# Becca_Sap_Flow_Power_Board_v1_3.net
KiCad netlist of a schematic drawn in EAGLE
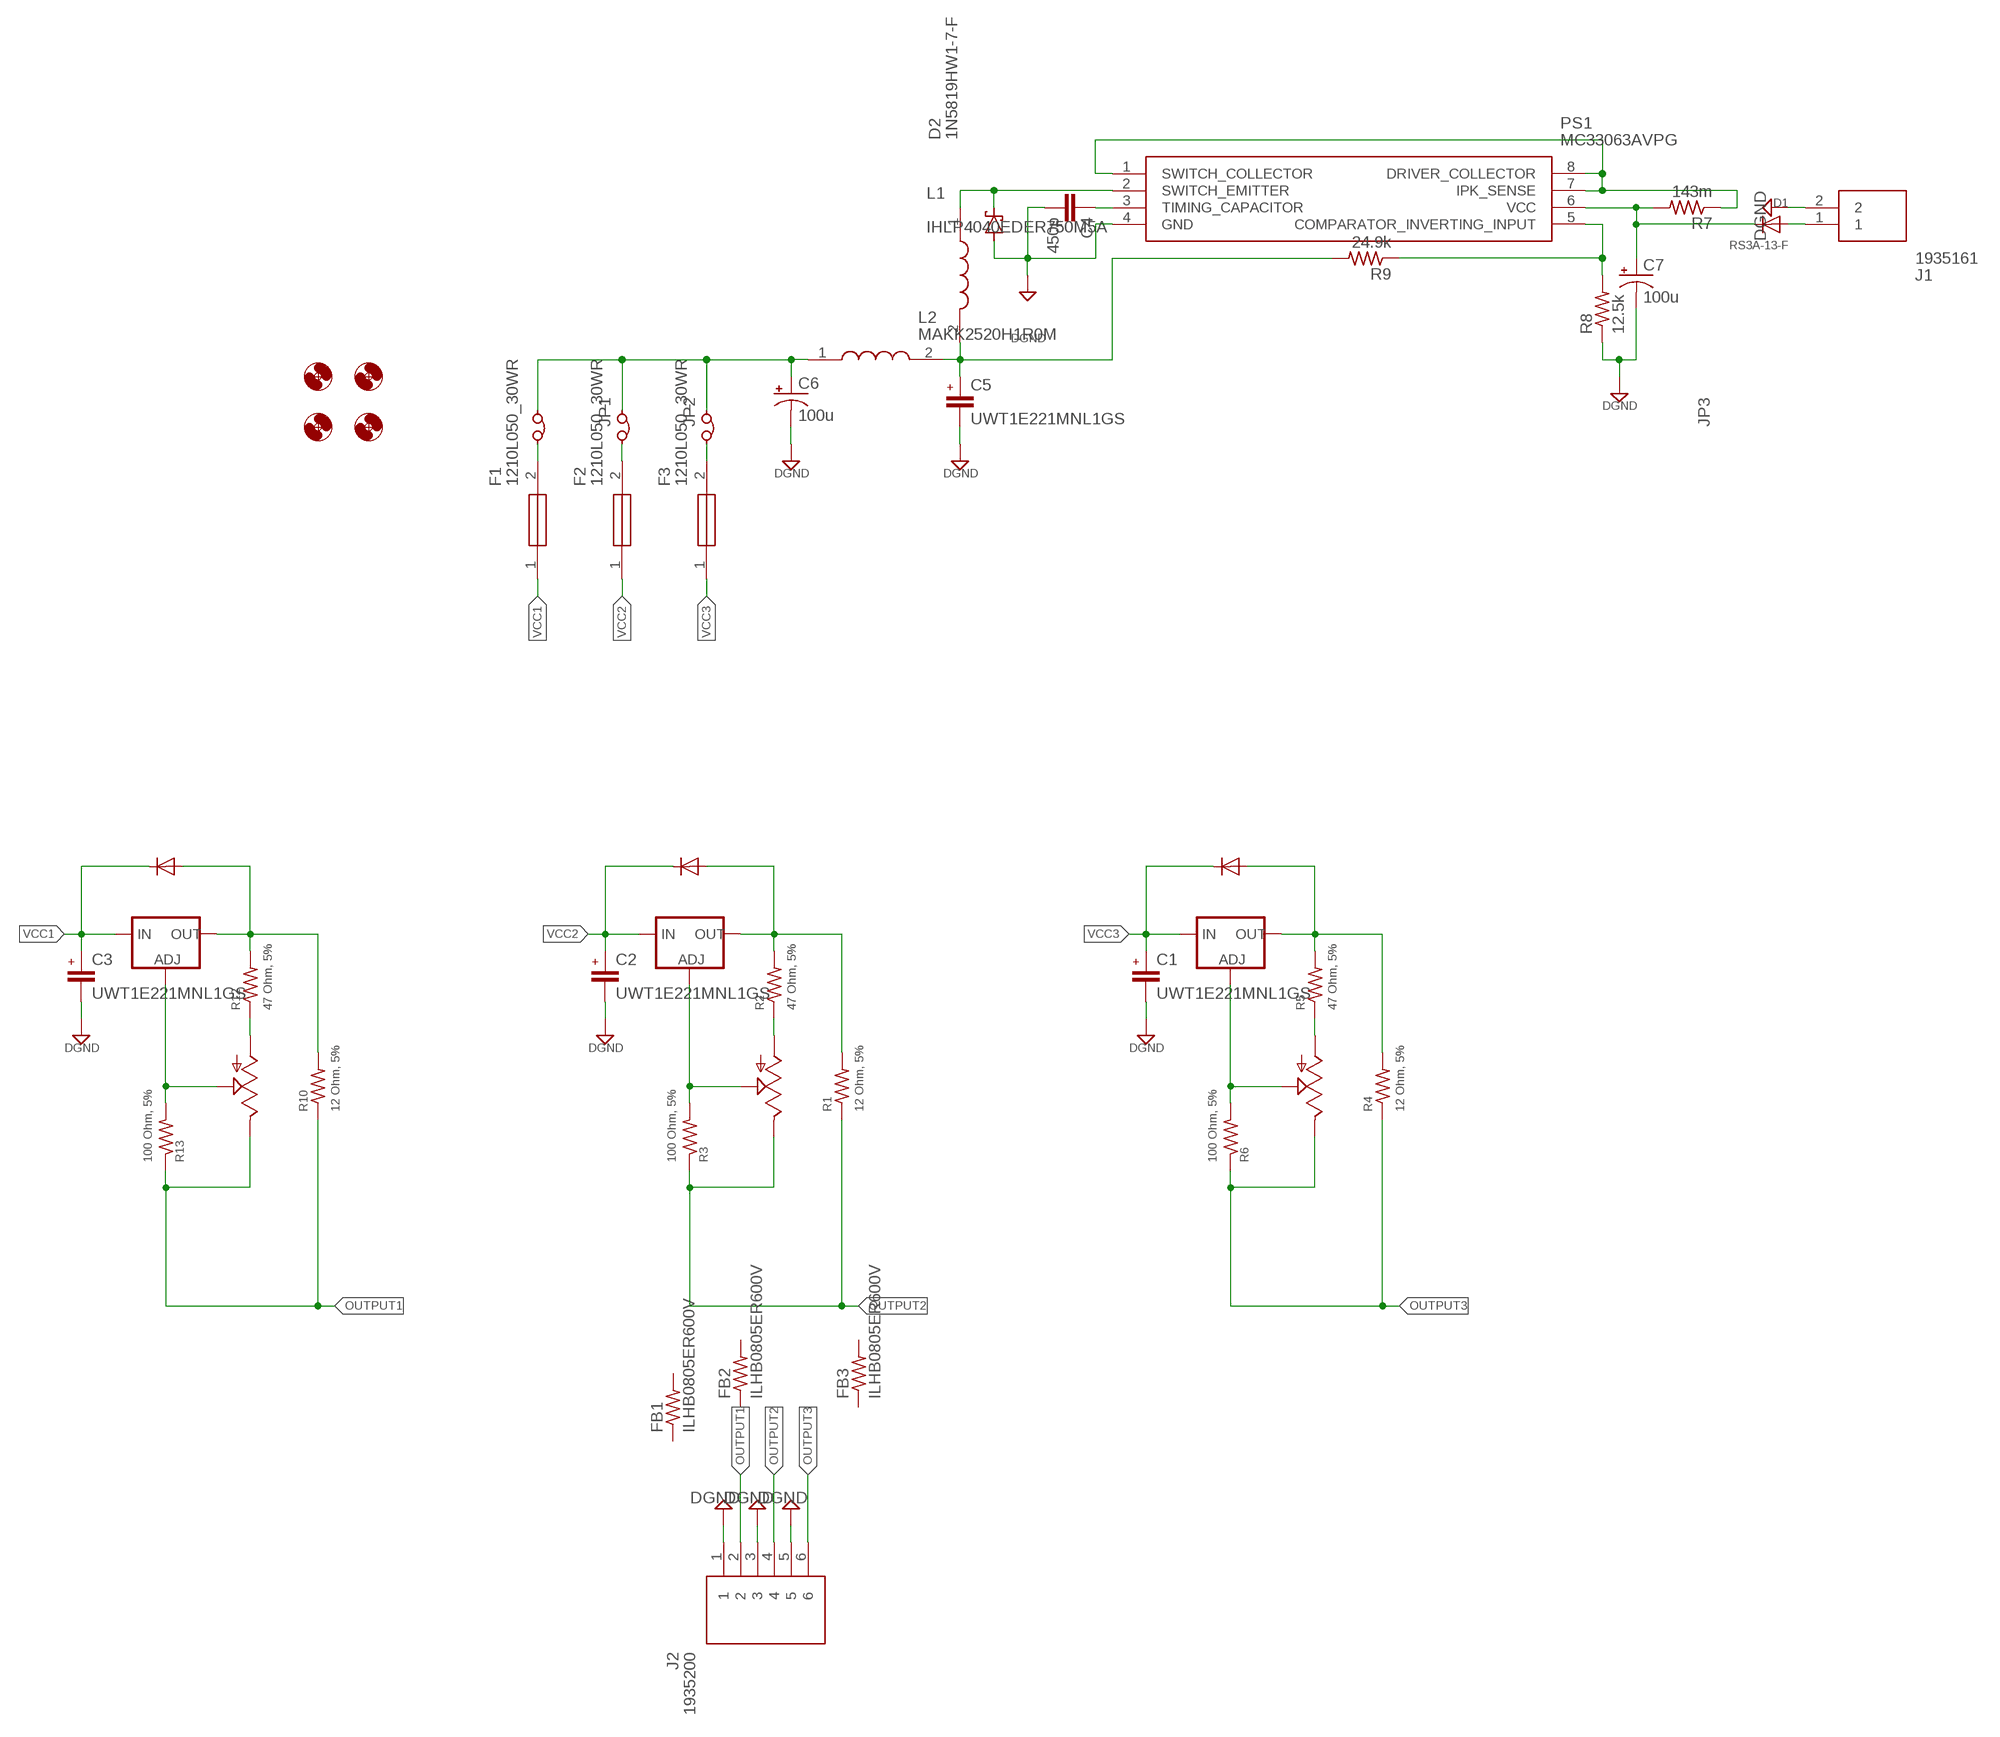
[diagram p0: schematic, sheet 1]

(export (version "E")
  (design (tool "Eeschema 10.0.6"))
  (components
    (comp (ref "C1")
      (value "UWT1E221MNL1GS")
      (footprint "eagle-import:CAPAE830X1080N")
      (fields (field (name "MOUSER_PART_NUMBER") "647-UWT1E221MNL1GS"))
      (libsource (lib "eagle-import") (part "UWT1E221MNL1GS"))
    )
    (comp (ref "C2")
      (value "UWT1E221MNL1GS")
      (footprint "eagle-import:CAPAE830X1080N")
      (fields (field (name "MOUSER_PART_NUMBER") "647-UWT1E221MNL1GS"))
      (libsource (lib "eagle-import") (part "UWT1E221MNL1GS"))
    )
    (comp (ref "C3")
      (value "UWT1E221MNL1GS")
      (footprint "eagle-import:CAPAE830X1080N")
      (fields (field (name "MOUSER_PART_NUMBER") "647-UWT1E221MNL1GS"))
      (libsource (lib "eagle-import") (part "UWT1E221MNL1GS"))
    )
    (comp (ref "C4")
      (value "450p")
      (footprint "eagle-import:C0603")
      (libsource (lib "eagle-import") (part "C-EUC0603"))
    )
    (comp (ref "C5")
      (value "UWT1E221MNL1GS")
      (footprint "eagle-import:CAPAE830X1080N")
      (fields (field (name "MOUSER_PART_NUMBER") "647-UWT1E221MNL1GS"))
      (libsource (lib "eagle-import") (part "UWT1E221MNL1GS"))
    )
    (comp (ref "C6")
      (value "100u")
      (footprint "eagle-import:E2,5-6")
      (libsource (lib "eagle-import") (part "CPOL-USE2.5-6"))
    )
    (comp (ref "C7")
      (value "100u")
      (footprint "eagle-import:E2,5-6")
      (libsource (lib "eagle-import") (part "CPOL-USE2.5-6"))
    )
    (comp (ref "D1")
      (value "RS3A-13-F")
      (footprint "eagle-import:DIOM7959X250N")
      (fields (field (name "MOUSER_PART_NUMBER") "621-RS3A-13-F"))
      (libsource (lib "eagle-import") (part "RS3A-13-F"))
    )
    (comp (ref "D2")
      (value "1N5819HW1-7-F")
      (footprint "eagle-import:SODFL3518X115N")
      (fields (field (name "MOUSER_PART_NUMBER") "621-1N5819HW1-7-F"))
      (libsource (lib "eagle-import") (part "1N5819HW1-7-F"))
    )
    (comp (ref "D3")
      (value "S1A")
      (footprint "eagle-import:DIOM5027X250N")
      (fields (field (name "MOUSER_PART_NUMBER") "637-S1A"))
      (libsource (lib "eagle-import") (part "S1A"))
    )
    (comp (ref "D4")
      (value "S1A")
      (footprint "eagle-import:DIOM5027X250N")
      (fields (field (name "MOUSER_PART_NUMBER") "637-S1A"))
      (libsource (lib "eagle-import") (part "S1A"))
    )
    (comp (ref "D6")
      (value "S1A")
      (footprint "eagle-import:DIOM5027X250N")
      (fields (field (name "MOUSER_PART_NUMBER") "637-S1A"))
      (libsource (lib "eagle-import") (part "S1A"))
    )
    (comp (ref "F1")
      (value "1210L050_30WR")
      (footprint "eagle-import:THRMC3226X125N")
      (fields
        (field (name "MANUFACTURER_PART_NUMBER") "1210L050/30WR")
        (field (name "MOUSER_PART_NUMBER") "576-1210L050/30WR")
      )
      (libsource (lib "eagle-import") (part "1210L050_30WR"))
    )
    (comp (ref "F2")
      (value "1210L050_30WR")
      (footprint "eagle-import:THRMC3226X125N")
      (fields
        (field (name "MANUFACTURER_PART_NUMBER") "1210L050/30WR")
        (field (name "MOUSER_PART_NUMBER") "576-1210L050/30WR")
      )
      (libsource (lib "eagle-import") (part "1210L050_30WR"))
    )
    (comp (ref "F3")
      (value "1210L050_30WR")
      (footprint "eagle-import:THRMC3226X125N")
      (fields
        (field (name "MANUFACTURER_PART_NUMBER") "1210L050/30WR")
        (field (name "MOUSER_PART_NUMBER") "576-1210L050/30WR")
      )
      (libsource (lib "eagle-import") (part "1210L050_30WR"))
    )
    (comp (ref "FB1")
      (value "ILHB0805ER600V")
      (footprint "eagle-import:BEADC2012X110N")
      (fields (field (name "MOUSER_PART_NUMBER") "70-ILHB0805ER600V"))
      (libsource (lib "eagle-import") (part "ILHB0805ER600V"))
    )
    (comp (ref "FB2")
      (value "ILHB0805ER600V")
      (footprint "eagle-import:BEADC2012X110N")
      (fields (field (name "MOUSER_PART_NUMBER") "70-ILHB0805ER600V"))
      (libsource (lib "eagle-import") (part "ILHB0805ER600V"))
    )
    (comp (ref "FB3")
      (value "ILHB0805ER600V")
      (footprint "eagle-import:BEADC2012X110N")
      (fields (field (name "MOUSER_PART_NUMBER") "70-ILHB0805ER600V"))
      (libsource (lib "eagle-import") (part "ILHB0805ER600V"))
    )
    (comp (ref "J1")
      (value "1935161")
      (footprint "eagle-import:1935161")
      (fields (field (name "MOUSER_PART_NUMBER") "651-1935161"))
      (libsource (lib "eagle-import") (part "1935161"))
    )
    (comp (ref "J2")
      (value "1935200")
      (footprint "eagle-import:1935200")
      (fields (field (name "MOUSER_PART_NUMBER") "651-1935200"))
      (libsource (lib "eagle-import") (part "1935200"))
    )
    (comp (ref "JP1")
      (value "JUMPER")
      (footprint "eagle-import:HDR2X1")
      (libsource (lib "eagle-import") (part "JUMPER"))
    )
    (comp (ref "JP2")
      (value "JUMPER")
      (footprint "eagle-import:HDR2X1")
      (libsource (lib "eagle-import") (part "JUMPER"))
    )
    (comp (ref "JP3")
      (value "JUMPER")
      (footprint "eagle-import:HDR2X1")
      (libsource (lib "eagle-import") (part "JUMPER"))
    )
    (comp (ref "L1")
      (value "IHLP4040EDER750M5A")
      (footprint "eagle-import:INDPM115103X540N")
      (fields (field (name "MOUSER_PART_NUMBER") "70-IHLP4040EDR750M5A"))
      (libsource (lib "eagle-import") (part "IHLP4040EDER750M5A"))
    )
    (comp (ref "L2")
      (value "MAKK2520H1R0M")
      (footprint "eagle-import:MAKK2520H1R0M")
      (fields (field (name "MOUSER_PART_NUMBER") "963-MAKK2520H1R0M"))
      (libsource (lib "eagle-import") (part "MAKK2520H1R0M"))
    )
    (comp (ref "PS1")
      (value "MC33063AVPG")
      (footprint "eagle-import:DIP794W56P254L959H533Q8N")
      (libsource (lib "eagle-import") (part "MC33063AVPG"))
    )
    (comp (ref "R1")
      (value "12 Ohm, 5%")
      (footprint "eagle-import:R1210")
      (libsource (lib "eagle-import") (part "R-US_R1210"))
    )
    (comp (ref "R2")
      (value "47 Ohm, 5%")
      (footprint "eagle-import:R1210")
      (libsource (lib "eagle-import") (part "R-US_R1210"))
    )
    (comp (ref "R3")
      (value "100 Ohm, 5%")
      (footprint "eagle-import:R1210")
      (libsource (lib "eagle-import") (part "R-US_R1210"))
    )
    (comp (ref "R4")
      (value "12 Ohm, 5%")
      (footprint "eagle-import:R1210")
      (libsource (lib "eagle-import") (part "R-US_R1210"))
    )
    (comp (ref "R5")
      (value "47 Ohm, 5%")
      (footprint "eagle-import:R1210")
      (libsource (lib "eagle-import") (part "R-US_R1210"))
    )
    (comp (ref "R6")
      (value "100 Ohm, 5%")
      (footprint "eagle-import:R1210")
      (libsource (lib "eagle-import") (part "R-US_R1210"))
    )
    (comp (ref "R7")
      (value "143m")
      (footprint "eagle-import:R0603")
      (libsource (lib "eagle-import") (part "R-US_R0603"))
    )
    (comp (ref "R8")
      (value "12.5k")
      (footprint "eagle-import:R0603")
      (libsource (lib "eagle-import") (part "R-US_R0603"))
    )
    (comp (ref "R9")
      (value "24.9k")
      (footprint "eagle-import:R0603")
      (libsource (lib "eagle-import") (part "R-US_R0603"))
    )
    (comp (ref "R10")
      (value "12 Ohm, 5%")
      (footprint "eagle-import:R1210")
      (libsource (lib "eagle-import") (part "R-US_R1210"))
    )
    (comp (ref "R12")
      (value "47 Ohm, 5%")
      (footprint "eagle-import:R1210")
      (libsource (lib "eagle-import") (part "R-US_R1210"))
    )
    (comp (ref "R13")
      (value "100 Ohm, 5%")
      (footprint "eagle-import:R1210")
      (libsource (lib "eagle-import") (part "R-US_R1210"))
    )
    (comp (ref "U$1")
      (value "MOUNT-HOLE3.0")
      (footprint "eagle-import:3,0")
      (libsource (lib "eagle-import") (part "MOUNT-HOLE3.0"))
    )
    (comp (ref "U$2")
      (value "MOUNT-HOLE3.0")
      (footprint "eagle-import:3,0")
      (libsource (lib "eagle-import") (part "MOUNT-HOLE3.0"))
    )
    (comp (ref "U$3")
      (value "MOUNT-HOLE3.0")
      (footprint "eagle-import:3,0")
      (libsource (lib "eagle-import") (part "MOUNT-HOLE3.0"))
    )
    (comp (ref "U$4")
      (value "MOUNT-HOLE3.0")
      (footprint "eagle-import:3,0")
      (libsource (lib "eagle-import") (part "MOUNT-HOLE3.0"))
    )
    (comp (ref "U1")
      (value "LM317MBSTT3G")
      (footprint "eagle-import:SOT230P700X175-4N")
      (fields (field (name "MOUSER_PART_NUMBER") "863-LM317MBSTT3G"))
      (libsource (lib "eagle-import") (part "LM317MBSTT3G"))
    )
    (comp (ref "U2")
      (value "LM317MBSTT3G")
      (footprint "eagle-import:SOT230P700X175-4N")
      (fields (field (name "MOUSER_PART_NUMBER") "863-LM317MBSTT3G"))
      (libsource (lib "eagle-import") (part "LM317MBSTT3G"))
    )
    (comp (ref "U3")
      (value "LM317MBSTT3G")
      (footprint "eagle-import:SOT230P700X175-4N")
      (fields (field (name "MOUSER_PART_NUMBER") "863-LM317MBSTT3G"))
      (libsource (lib "eagle-import") (part "LM317MBSTT3G"))
    )
    (comp (ref "VR1")
      (value "3296W-1-102RLF")
      (footprint "eagle-import:3296W1102RLF")
      (fields (field (name "MOUSER_PART_NUMBER") "652-3296W-1-102RLF"))
      (libsource (lib "eagle-import") (part "3296W-1-102RLF"))
    )
    (comp (ref "VR2")
      (value "3296W-1-102RLF")
      (footprint "eagle-import:3296W1102RLF")
      (fields (field (name "MOUSER_PART_NUMBER") "652-3296W-1-102RLF"))
      (libsource (lib "eagle-import") (part "3296W-1-102RLF"))
    )
    (comp (ref "VR3")
      (value "3296W-1-102RLF")
      (footprint "eagle-import:3296W1102RLF")
      (fields (field (name "MOUSER_PART_NUMBER") "652-3296W-1-102RLF"))
      (libsource (lib "eagle-import") (part "3296W-1-102RLF"))
    )
  )
  (nets
    (net (code "1") (name "DGND") (class "Default")
      (node (ref "C1") (pin "2") (pinfunction "2_2") (pintype "passive"))
      (node (ref "C2") (pin "2") (pinfunction "2_2") (pintype "passive"))
      (node (ref "C3") (pin "2") (pinfunction "2_2") (pintype "passive"))
      (node (ref "C4") (pin "2") (pinfunction "2_2") (pintype "passive"))
      (node (ref "C5") (pin "2") (pinfunction "2_2") (pintype "passive"))
      (node (ref "C6") (pin "-") (pinfunction "-_-") (pintype "passive"))
      (node (ref "C7") (pin "-") (pinfunction "-_-") (pintype "passive"))
      (node (ref "D2") (pin "2") (pinfunction "A_2") (pintype "passive"))
      (node (ref "J1") (pin "2") (pinfunction "2_2") (pintype "bidirectional"))
      (node (ref "J2") (pin "1") (pinfunction "1_1") (pintype "bidirectional"))
      (node (ref "J2") (pin "3") (pinfunction "3_3") (pintype "bidirectional"))
      (node (ref "J2") (pin "5") (pinfunction "5_5") (pintype "bidirectional"))
      (node (ref "PS1") (pin "4") (pinfunction "GND_4") (pintype "bidirectional"))
      (node (ref "R8") (pin "1") (pinfunction "1_1") (pintype "passive"))
    )
    (net (code "2") (name "Net-(C5-Pad1)") (class "Default")
      (node (ref "C5") (pin "1") (pinfunction "1_1") (pintype "passive"))
      (node (ref "L1") (pin "2") (pinfunction "2_2") (pintype "bidirectional"))
      (node (ref "L2") (pin "2") (pinfunction "2_2") (pintype "bidirectional"))
      (node (ref "R9") (pin "2") (pinfunction "2_2") (pintype "passive"))
    )
    (net (code "3") (name "Net-(C6-Pad+)") (class "Default")
      (node (ref "C6") (pin "+") (pinfunction "+_+") (pintype "passive"))
      (node (ref "JP1") (pin "1") (pinfunction "1_1") (pintype "passive"))
      (node (ref "JP2") (pin "1") (pinfunction "1_1") (pintype "passive"))
      (node (ref "JP3") (pin "1") (pinfunction "1_1") (pintype "passive"))
      (node (ref "L2") (pin "1") (pinfunction "1_1") (pintype "bidirectional"))
    )
    (net (code "4") (name "Net-(D1-A)") (class "Default")
      (node (ref "D1") (pin "2") (pinfunction "A_2") (pintype "passive"))
      (node (ref "J1") (pin "1") (pinfunction "1_1") (pintype "bidirectional"))
    )
    (net (code "5") (name "Net-(D1-K)") (class "Default")
      (node (ref "C7") (pin "+") (pinfunction "+_+") (pintype "passive"))
      (node (ref "D1") (pin "1") (pinfunction "K_1") (pintype "passive"))
      (node (ref "PS1") (pin "6") (pinfunction "VCC_6") (pintype "bidirectional"))
      (node (ref "R7") (pin "2") (pinfunction "2_2") (pintype "passive"))
    )
    (net (code "6") (name "Net-(D2-C)") (class "Default")
      (node (ref "D2") (pin "1") (pinfunction "C_1") (pintype "passive"))
      (node (ref "L1") (pin "1") (pinfunction "1_1") (pintype "bidirectional"))
      (node (ref "PS1") (pin "2") (pinfunction "SWITCH_EMITTER_2") (pintype "bidirectional"))
    )
    (net (code "7") (name "Net-(D3-A)") (class "Default")
      (node (ref "D3") (pin "2") (pinfunction "A_2") (pintype "passive"))
      (node (ref "R1") (pin "2") (pinfunction "2_2") (pintype "passive"))
      (node (ref "R2") (pin "2") (pinfunction "2_2") (pintype "passive"))
      (node (ref "U2") (pin "2") (pinfunction "OUT_2") (pintype "output"))
    )
    (net (code "8") (name "Net-(D4-A)") (class "Default")
      (node (ref "D4") (pin "2") (pinfunction "A_2") (pintype "passive"))
      (node (ref "R4") (pin "2") (pinfunction "2_2") (pintype "passive"))
      (node (ref "R5") (pin "2") (pinfunction "2_2") (pintype "passive"))
      (node (ref "U3") (pin "2") (pinfunction "OUT_2") (pintype "output"))
    )
    (net (code "9") (name "Net-(D6-A)") (class "Default")
      (node (ref "D6") (pin "2") (pinfunction "A_2") (pintype "passive"))
      (node (ref "R10") (pin "2") (pinfunction "2_2") (pintype "passive"))
      (node (ref "R12") (pin "2") (pinfunction "2_2") (pintype "passive"))
      (node (ref "U1") (pin "2") (pinfunction "OUT_2") (pintype "output"))
    )
    (net (code "10") (name "Net-(F1-Pad2)") (class "Default")
      (node (ref "F1") (pin "2") (pinfunction "2_2") (pintype "bidirectional"))
      (node (ref "JP3") (pin "2") (pinfunction "2_2") (pintype "passive"))
    )
    (net (code "11") (name "Net-(F2-Pad2)") (class "Default")
      (node (ref "F2") (pin "2") (pinfunction "2_2") (pintype "bidirectional"))
      (node (ref "JP1") (pin "2") (pinfunction "2_2") (pintype "passive"))
    )
    (net (code "12") (name "Net-(F3-Pad2)") (class "Default")
      (node (ref "F3") (pin "2") (pinfunction "2_2") (pintype "bidirectional"))
      (node (ref "JP2") (pin "2") (pinfunction "2_2") (pintype "passive"))
    )
    (net (code "13") (name "Net-(PS1-COMPARATOR_INVERTING_INPUT)") (class "Default")
      (node (ref "PS1") (pin "5") (pinfunction "COMPARATOR_INVERTING_INPUT_5") (pintype "bidirectional"))
      (node (ref "R8") (pin "2") (pinfunction "2_2") (pintype "passive"))
      (node (ref "R9") (pin "1") (pinfunction "1_1") (pintype "passive"))
    )
    (net (code "14") (name "Net-(PS1-DRIVER_COLLECTOR)") (class "Default")
      (node (ref "PS1") (pin "1") (pinfunction "SWITCH_COLLECTOR_1") (pintype "bidirectional"))
      (node (ref "PS1") (pin "7") (pinfunction "IPK_SENSE_7") (pintype "bidirectional"))
      (node (ref "PS1") (pin "8") (pinfunction "DRIVER_COLLECTOR_8") (pintype "bidirectional"))
      (node (ref "R7") (pin "1") (pinfunction "1_1") (pintype "passive"))
    )
    (net (code "15") (name "Net-(PS1-TIMING_CAPACITOR)") (class "Default")
      (node (ref "C4") (pin "1") (pinfunction "1_1") (pintype "passive"))
      (node (ref "PS1") (pin "3") (pinfunction "TIMING_CAPACITOR_3") (pintype "bidirectional"))
    )
    (net (code "16") (name "Net-(U1-ADJ)") (class "Default")
      (node (ref "R13") (pin "2") (pinfunction "2_2") (pintype "passive"))
      (node (ref "U1") (pin "1") (pinfunction "ADJ_1") (pintype "input"))
      (node (ref "VR1") (pin "2") (pinfunction "S_2") (pintype "passive"))
    )
    (net (code "17") (name "Net-(U2-ADJ)") (class "Default")
      (node (ref "R3") (pin "2") (pinfunction "2_2") (pintype "passive"))
      (node (ref "U2") (pin "1") (pinfunction "ADJ_1") (pintype "input"))
      (node (ref "VR2") (pin "2") (pinfunction "S_2") (pintype "passive"))
    )
    (net (code "18") (name "Net-(U3-ADJ)") (class "Default")
      (node (ref "R6") (pin "2") (pinfunction "2_2") (pintype "passive"))
      (node (ref "U3") (pin "1") (pinfunction "ADJ_1") (pintype "input"))
      (node (ref "VR3") (pin "2") (pinfunction "S_2") (pintype "passive"))
    )
    (net (code "19") (name "Net-(VR1-A)") (class "Default")
      (node (ref "R12") (pin "1") (pinfunction "1_1") (pintype "passive"))
      (node (ref "VR1") (pin "1") (pinfunction "A_1") (pintype "passive"))
    )
    (net (code "20") (name "Net-(VR2-A)") (class "Default")
      (node (ref "R2") (pin "1") (pinfunction "1_1") (pintype "passive"))
      (node (ref "VR2") (pin "1") (pinfunction "A_1") (pintype "passive"))
    )
    (net (code "21") (name "Net-(VR3-A)") (class "Default")
      (node (ref "R5") (pin "1") (pinfunction "1_1") (pintype "passive"))
      (node (ref "VR3") (pin "1") (pinfunction "A_1") (pintype "passive"))
    )
    (net (code "22") (name "OUTPUT1") (class "Default")
      (node (ref "J2") (pin "2") (pinfunction "2_2") (pintype "bidirectional"))
      (node (ref "R10") (pin "1") (pinfunction "1_1") (pintype "passive"))
      (node (ref "R13") (pin "1") (pinfunction "1_1") (pintype "passive"))
      (node (ref "VR1") (pin "3") (pinfunction "E_3") (pintype "passive"))
    )
    (net (code "23") (name "OUTPUT2") (class "Default")
      (node (ref "J2") (pin "4") (pinfunction "4_4") (pintype "bidirectional"))
      (node (ref "R1") (pin "1") (pinfunction "1_1") (pintype "passive"))
      (node (ref "R3") (pin "1") (pinfunction "1_1") (pintype "passive"))
      (node (ref "VR2") (pin "3") (pinfunction "E_3") (pintype "passive"))
    )
    (net (code "24") (name "OUTPUT3") (class "Default")
      (node (ref "J2") (pin "6") (pinfunction "6_6") (pintype "bidirectional"))
      (node (ref "R4") (pin "1") (pinfunction "1_1") (pintype "passive"))
      (node (ref "R6") (pin "1") (pinfunction "1_1") (pintype "passive"))
      (node (ref "VR3") (pin "3") (pinfunction "E_3") (pintype "passive"))
    )
    (net (code "25") (name "VCC1") (class "Default")
      (node (ref "C3") (pin "1") (pinfunction "1_1") (pintype "passive"))
      (node (ref "D6") (pin "1") (pinfunction "K_1") (pintype "passive"))
      (node (ref "F1") (pin "1") (pinfunction "1_1") (pintype "bidirectional"))
      (node (ref "U1") (pin "3") (pinfunction "IN_3") (pintype "input"))
    )
    (net (code "26") (name "VCC2") (class "Default")
      (node (ref "C2") (pin "1") (pinfunction "1_1") (pintype "passive"))
      (node (ref "D3") (pin "1") (pinfunction "K_1") (pintype "passive"))
      (node (ref "F2") (pin "1") (pinfunction "1_1") (pintype "bidirectional"))
      (node (ref "U2") (pin "3") (pinfunction "IN_3") (pintype "input"))
    )
    (net (code "27") (name "VCC3") (class "Default")
      (node (ref "C1") (pin "1") (pinfunction "1_1") (pintype "passive"))
      (node (ref "D4") (pin "1") (pinfunction "K_1") (pintype "passive"))
      (node (ref "F3") (pin "1") (pinfunction "1_1") (pintype "bidirectional"))
      (node (ref "U3") (pin "3") (pinfunction "IN_3") (pintype "input"))
    )
    (net (code "28") (name "unconnected-(FB1-Pad1)") (class "Default")
      (node (ref "FB1") (pin "1") (pinfunction "1_1") (pintype "passive"))
    )
    (net (code "29") (name "unconnected-(FB1-Pad2)") (class "Default")
      (node (ref "FB1") (pin "2") (pinfunction "2_2") (pintype "passive"))
    )
    (net (code "30") (name "unconnected-(FB2-Pad1)") (class "Default")
      (node (ref "FB2") (pin "1") (pinfunction "1_1") (pintype "passive"))
    )
    (net (code "31") (name "unconnected-(FB2-Pad2)") (class "Default")
      (node (ref "FB2") (pin "2") (pinfunction "2_2") (pintype "passive"))
    )
    (net (code "32") (name "unconnected-(FB3-Pad1)") (class "Default")
      (node (ref "FB3") (pin "1") (pinfunction "1_1") (pintype "passive"))
    )
    (net (code "33") (name "unconnected-(FB3-Pad2)") (class "Default")
      (node (ref "FB3") (pin "2") (pinfunction "2_2") (pintype "passive"))
    )
  )
)
